# Wave_X_Motor_Drivers.net
KiCad netlist of a schematic drawn in EAGLE
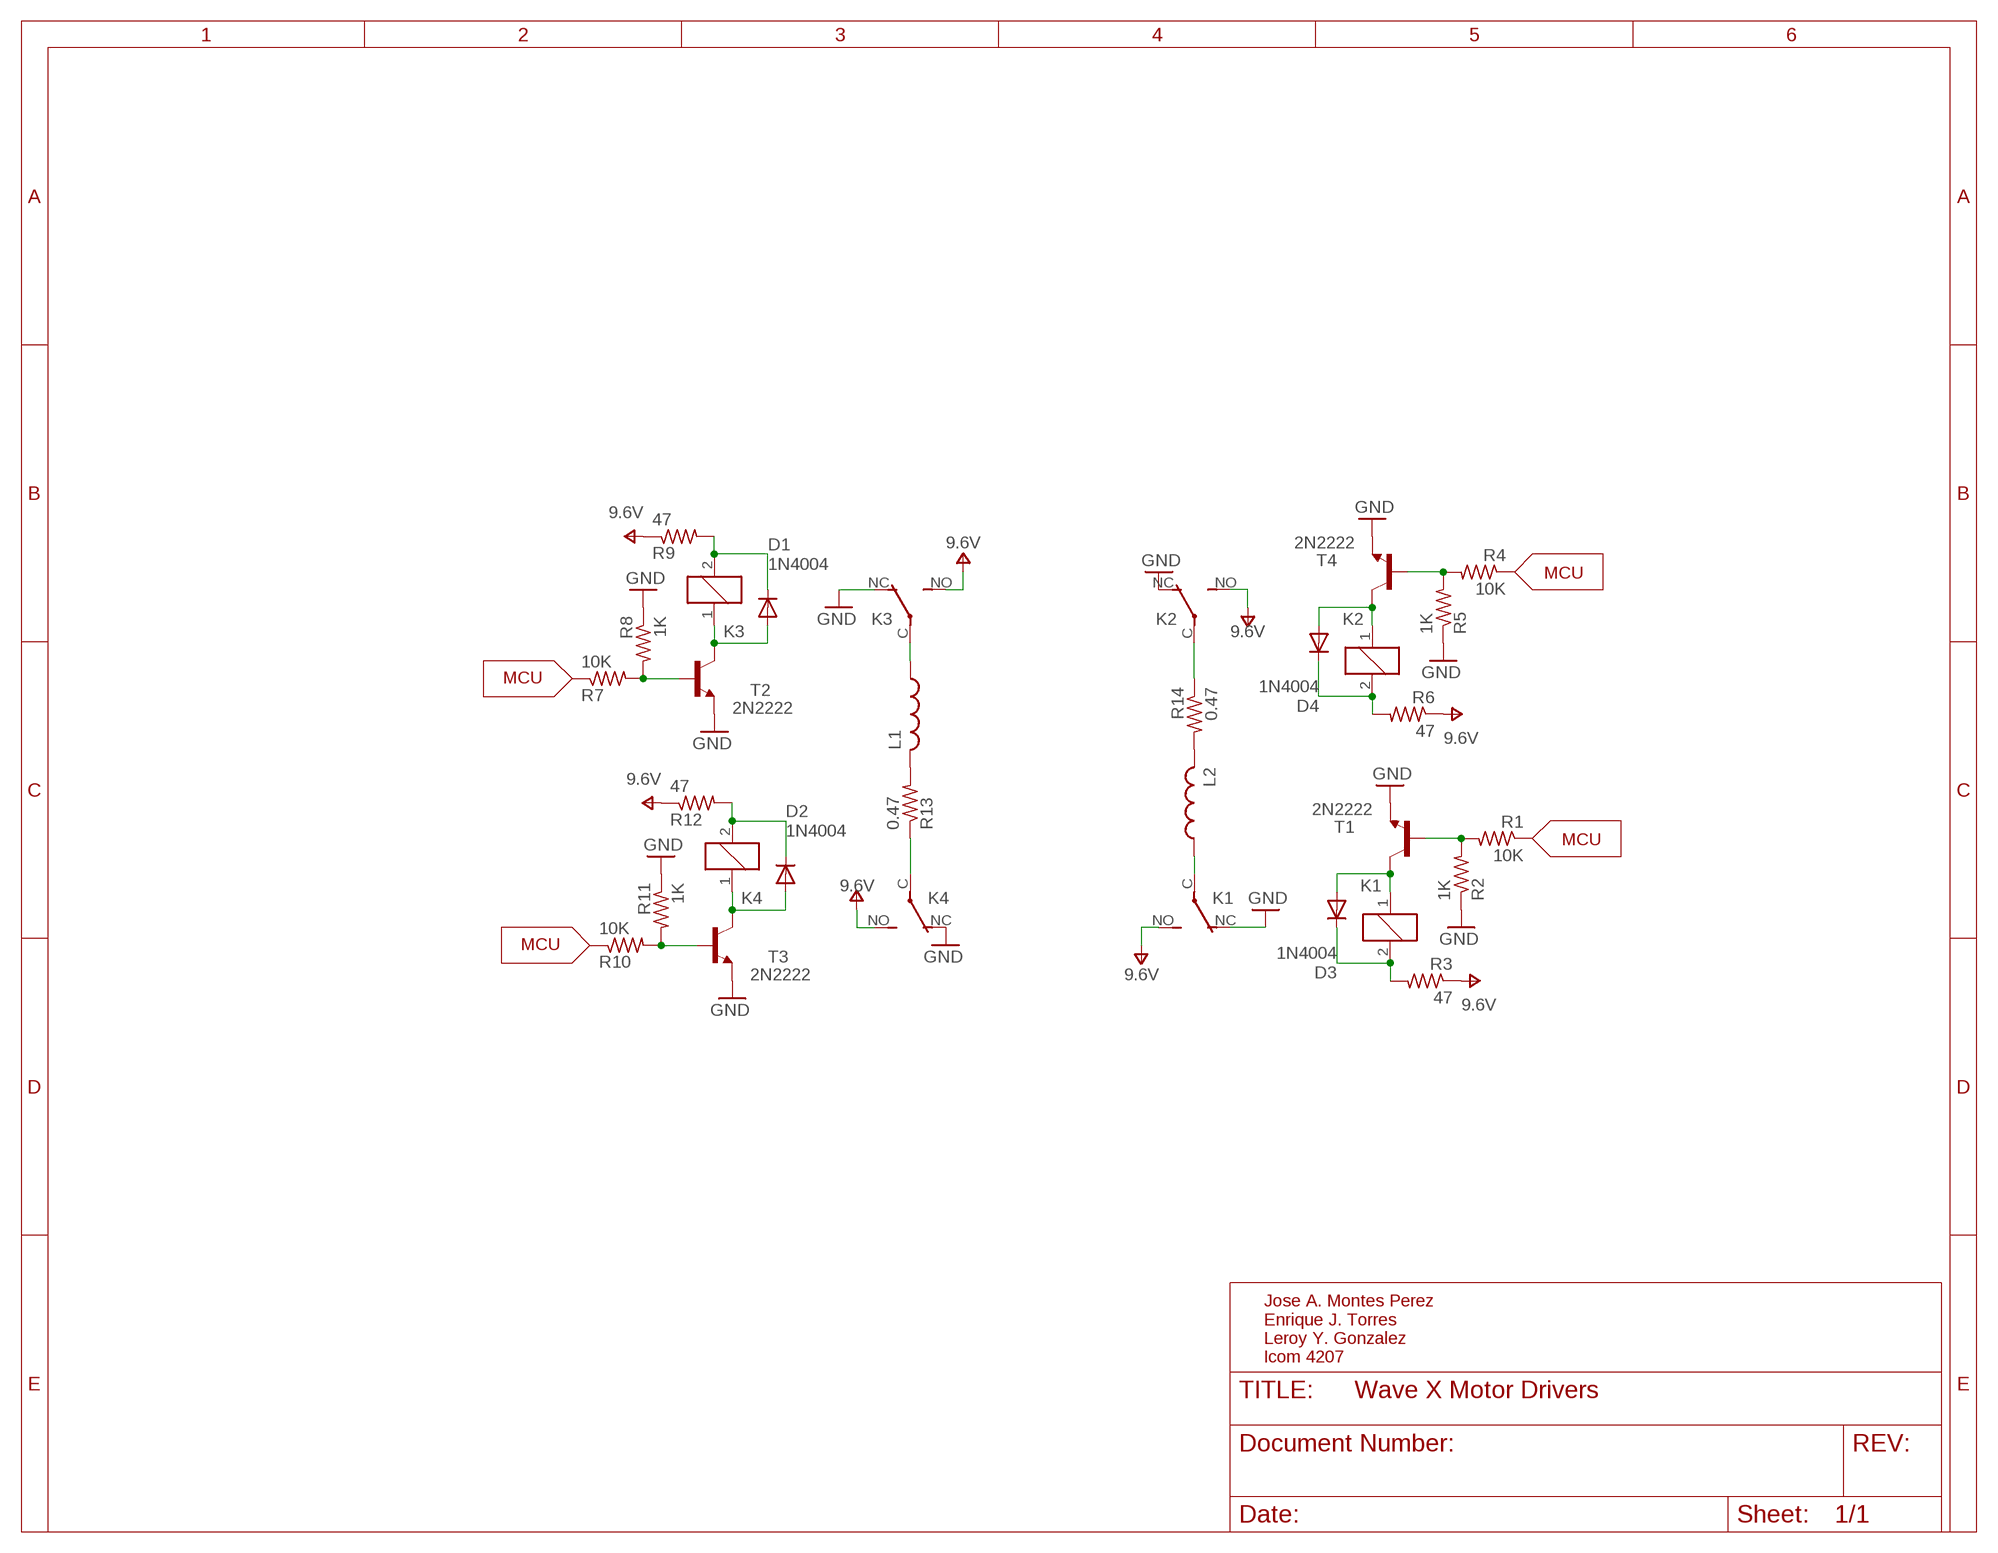
[diagram p0: schematic, sheet 1]

(export (version "E")
  (design (tool "Eeschema 10.0.6"))
  (components
    (comp (ref "D1")
      (value "1N4004")
      (footprint "eagle-import:DO41-10")
      (libsource (lib "eagle-import") (part "1N4004"))
    )
    (comp (ref "D2")
      (value "1N4004")
      (footprint "eagle-import:DO41-10")
      (libsource (lib "eagle-import") (part "1N4004"))
    )
    (comp (ref "D3")
      (value "1N4004")
      (footprint "eagle-import:DO41-10")
      (libsource (lib "eagle-import") (part "1N4004"))
    )
    (comp (ref "D4")
      (value "1N4004")
      (footprint "eagle-import:DO41-10")
      (libsource (lib "eagle-import") (part "1N4004"))
    )
    (comp (ref "K1")
      (value "JJM1-12V")
      (footprint "eagle-import:JJM1C")
      (fields (field (name "MF") "AROMAT/ MATSUSHITA"))
      (libsource (lib "eagle-import") (part "JJM1-12V"))
    )
    (comp (ref "K2")
      (value "JJM1-12V")
      (footprint "eagle-import:JJM1C")
      (fields (field (name "MF") "AROMAT/ MATSUSHITA"))
      (libsource (lib "eagle-import") (part "JJM1-12V"))
    )
    (comp (ref "K3")
      (value "JJM1-12V")
      (footprint "eagle-import:JJM1C")
      (fields (field (name "MF") "AROMAT/ MATSUSHITA"))
      (libsource (lib "eagle-import") (part "JJM1-12V"))
    )
    (comp (ref "K4")
      (value "JJM1-12V")
      (footprint "eagle-import:JJM1C")
      (fields (field (name "MF") "AROMAT/ MATSUSHITA"))
      (libsource (lib "eagle-import") (part "JJM1-12V"))
    )
    (comp (ref "L1")
      (value "L-USL4532P")
      (footprint "eagle-import:L4532P")
      (libsource (lib "eagle-import") (part "L-USL4532P"))
    )
    (comp (ref "L2")
      (value "L-USL4532P")
      (footprint "eagle-import:L4532P")
      (libsource (lib "eagle-import") (part "L-USL4532P"))
    )
    (comp (ref "R1")
      (value "10K")
      (footprint "eagle-import:0207_7")
      (libsource (lib "eagle-import") (part "R-US_0207/7"))
    )
    (comp (ref "R2")
      (value "1K")
      (footprint "eagle-import:0207_7")
      (libsource (lib "eagle-import") (part "R-US_0207/7"))
    )
    (comp (ref "R3")
      (value "47")
      (footprint "eagle-import:0207_7")
      (libsource (lib "eagle-import") (part "R-US_0207/7"))
    )
    (comp (ref "R4")
      (value "10K")
      (footprint "eagle-import:0207_7")
      (libsource (lib "eagle-import") (part "R-US_0207/7"))
    )
    (comp (ref "R5")
      (value "1K")
      (footprint "eagle-import:0207_7")
      (libsource (lib "eagle-import") (part "R-US_0207/7"))
    )
    (comp (ref "R6")
      (value "47")
      (footprint "eagle-import:0207_7")
      (libsource (lib "eagle-import") (part "R-US_0207/7"))
    )
    (comp (ref "R7")
      (value "10K")
      (footprint "eagle-import:0207_7")
      (libsource (lib "eagle-import") (part "R-US_0207/7"))
    )
    (comp (ref "R8")
      (value "1K")
      (footprint "eagle-import:0207_7")
      (libsource (lib "eagle-import") (part "R-US_0207/7"))
    )
    (comp (ref "R9")
      (value "47")
      (footprint "eagle-import:0207_7")
      (libsource (lib "eagle-import") (part "R-US_0207/7"))
    )
    (comp (ref "R10")
      (value "10K")
      (footprint "eagle-import:0207_7")
      (libsource (lib "eagle-import") (part "R-US_0207/7"))
    )
    (comp (ref "R11")
      (value "1K")
      (footprint "eagle-import:0207_7")
      (libsource (lib "eagle-import") (part "R-US_0207/7"))
    )
    (comp (ref "R12")
      (value "47")
      (footprint "eagle-import:0207_7")
      (libsource (lib "eagle-import") (part "R-US_0207/7"))
    )
    (comp (ref "R13")
      (value "0.47")
      (footprint "eagle-import:0207_7")
      (libsource (lib "eagle-import") (part "R-US_0207/7"))
    )
    (comp (ref "R14")
      (value "0.47")
      (footprint "eagle-import:0207_7")
      (libsource (lib "eagle-import") (part "R-US_0207/7"))
    )
    (comp (ref "T1")
      (value "2N2222")
      (footprint "eagle-import:TO18")
      (libsource (lib "eagle-import") (part "2N2222"))
    )
    (comp (ref "T2")
      (value "2N2222")
      (footprint "eagle-import:TO18")
      (libsource (lib "eagle-import") (part "2N2222"))
    )
    (comp (ref "T3")
      (value "2N2222")
      (footprint "eagle-import:TO18")
      (libsource (lib "eagle-import") (part "2N2222"))
    )
    (comp (ref "T4")
      (value "2N2222")
      (footprint "eagle-import:TO18")
      (libsource (lib "eagle-import") (part "2N2222"))
    )
  )
  (nets
    (net (code "1") (name "9.6V") (class "Default")
      (node (ref "K1") (pin "NO") (pinfunction "S_NO") (pintype "passive"))
      (node (ref "K2") (pin "NO") (pinfunction "S_NO") (pintype "passive"))
      (node (ref "K3") (pin "NO") (pinfunction "S_NO") (pintype "passive"))
      (node (ref "K4") (pin "NO") (pinfunction "S_NO") (pintype "passive"))
      (node (ref "R12") (pin "1") (pinfunction "1_1") (pintype "passive"))
      (node (ref "R3") (pin "1") (pinfunction "1_1") (pintype "passive"))
      (node (ref "R6") (pin "1") (pinfunction "1_1") (pintype "passive"))
      (node (ref "R9") (pin "1") (pinfunction "1_1") (pintype "passive"))
    )
    (net (code "2") (name "GND") (class "Default")
      (node (ref "K1") (pin "NC") (pinfunction "O_NC") (pintype "passive"))
      (node (ref "K2") (pin "NC") (pinfunction "O_NC") (pintype "passive"))
      (node (ref "K3") (pin "NC") (pinfunction "O_NC") (pintype "passive"))
      (node (ref "K4") (pin "NC") (pinfunction "O_NC") (pintype "passive"))
      (node (ref "R11") (pin "1") (pinfunction "1_1") (pintype "passive"))
      (node (ref "R2") (pin "1") (pinfunction "1_1") (pintype "passive"))
      (node (ref "R5") (pin "1") (pinfunction "1_1") (pintype "passive"))
      (node (ref "R8") (pin "1") (pinfunction "1_1") (pintype "passive"))
      (node (ref "T1") (pin "1") (pinfunction "E_1") (pintype "passive"))
      (node (ref "T2") (pin "1") (pinfunction "E_1") (pintype "passive"))
      (node (ref "T3") (pin "1") (pinfunction "E_1") (pintype "passive"))
      (node (ref "T4") (pin "1") (pinfunction "E_1") (pintype "passive"))
    )
    (net (code "3") (name "Net-(D1-PadC)") (class "Default")
      (node (ref "D1") (pin "C") (pinfunction "C_C") (pintype "passive"))
      (node (ref "K3") (pin "2") (pinfunction "2_2") (pintype "passive"))
      (node (ref "R9") (pin "2") (pinfunction "2_2") (pintype "passive"))
    )
    (net (code "4") (name "Net-(D2-PadC)") (class "Default")
      (node (ref "D2") (pin "C") (pinfunction "C_C") (pintype "passive"))
      (node (ref "K4") (pin "2") (pinfunction "2_2") (pintype "passive"))
      (node (ref "R12") (pin "2") (pinfunction "2_2") (pintype "passive"))
    )
    (net (code "5") (name "Net-(D3-PadC)") (class "Default")
      (node (ref "D3") (pin "C") (pinfunction "C_C") (pintype "passive"))
      (node (ref "K1") (pin "2") (pinfunction "2_2") (pintype "passive"))
      (node (ref "R3") (pin "2") (pinfunction "2_2") (pintype "passive"))
    )
    (net (code "6") (name "Net-(D4-PadC)") (class "Default")
      (node (ref "D4") (pin "C") (pinfunction "C_C") (pintype "passive"))
      (node (ref "K2") (pin "2") (pinfunction "2_2") (pintype "passive"))
      (node (ref "R6") (pin "2") (pinfunction "2_2") (pintype "passive"))
    )
    (net (code "7") (name "Net-(K1B-P)") (class "Default")
      (node (ref "K1") (pin "C") (pinfunction "P_C") (pintype "passive"))
      (node (ref "L2") (pin "1") (pinfunction "1_1") (pintype "passive"))
    )
    (net (code "8") (name "Net-(K2B-P)") (class "Default")
      (node (ref "K2") (pin "C") (pinfunction "P_C") (pintype "passive"))
      (node (ref "R14") (pin "1") (pinfunction "1_1") (pintype "passive"))
    )
    (net (code "9") (name "Net-(K3B-P)") (class "Default")
      (node (ref "K3") (pin "C") (pinfunction "P_C") (pintype "passive"))
      (node (ref "L1") (pin "1") (pinfunction "1_1") (pintype "passive"))
    )
    (net (code "10") (name "Net-(K4B-P)") (class "Default")
      (node (ref "K4") (pin "C") (pinfunction "P_C") (pintype "passive"))
      (node (ref "R13") (pin "1") (pinfunction "1_1") (pintype "passive"))
    )
    (net (code "11") (name "Net-(L1-Pad2)") (class "Default")
      (node (ref "L1") (pin "2") (pinfunction "2_2") (pintype "passive"))
      (node (ref "R13") (pin "2") (pinfunction "2_2") (pintype "passive"))
    )
    (net (code "12") (name "Net-(L2-Pad2)") (class "Default")
      (node (ref "L2") (pin "2") (pinfunction "2_2") (pintype "passive"))
      (node (ref "R14") (pin "2") (pinfunction "2_2") (pintype "passive"))
    )
    (net (code "13") (name "Net-(T1-B)") (class "Default")
      (node (ref "R1") (pin "2") (pinfunction "2_2") (pintype "passive"))
      (node (ref "R2") (pin "2") (pinfunction "2_2") (pintype "passive"))
      (node (ref "T1") (pin "2") (pinfunction "B_2") (pintype "passive"))
    )
    (net (code "14") (name "Net-(T1-C)") (class "Default")
      (node (ref "D3") (pin "A") (pinfunction "A_A") (pintype "passive"))
      (node (ref "K1") (pin "1") (pinfunction "1_1") (pintype "passive"))
      (node (ref "T1") (pin "3") (pinfunction "C_3") (pintype "passive"))
    )
    (net (code "15") (name "Net-(T2-B)") (class "Default")
      (node (ref "R7") (pin "2") (pinfunction "2_2") (pintype "passive"))
      (node (ref "R8") (pin "2") (pinfunction "2_2") (pintype "passive"))
      (node (ref "T2") (pin "2") (pinfunction "B_2") (pintype "passive"))
    )
    (net (code "16") (name "Net-(T2-C)") (class "Default")
      (node (ref "D1") (pin "A") (pinfunction "A_A") (pintype "passive"))
      (node (ref "K3") (pin "1") (pinfunction "1_1") (pintype "passive"))
      (node (ref "T2") (pin "3") (pinfunction "C_3") (pintype "passive"))
    )
    (net (code "17") (name "Net-(T3-B)") (class "Default")
      (node (ref "R10") (pin "2") (pinfunction "2_2") (pintype "passive"))
      (node (ref "R11") (pin "2") (pinfunction "2_2") (pintype "passive"))
      (node (ref "T3") (pin "2") (pinfunction "B_2") (pintype "passive"))
    )
    (net (code "18") (name "Net-(T3-C)") (class "Default")
      (node (ref "D2") (pin "A") (pinfunction "A_A") (pintype "passive"))
      (node (ref "K4") (pin "1") (pinfunction "1_1") (pintype "passive"))
      (node (ref "T3") (pin "3") (pinfunction "C_3") (pintype "passive"))
    )
    (net (code "19") (name "Net-(T4-B)") (class "Default")
      (node (ref "R4") (pin "2") (pinfunction "2_2") (pintype "passive"))
      (node (ref "R5") (pin "2") (pinfunction "2_2") (pintype "passive"))
      (node (ref "T4") (pin "2") (pinfunction "B_2") (pintype "passive"))
    )
    (net (code "20") (name "Net-(T4-C)") (class "Default")
      (node (ref "D4") (pin "A") (pinfunction "A_A") (pintype "passive"))
      (node (ref "K2") (pin "1") (pinfunction "1_1") (pintype "passive"))
      (node (ref "T4") (pin "3") (pinfunction "C_3") (pintype "passive"))
    )
    (net (code "21") (name "unconnected-(R1-Pad1)") (class "Default")
      (node (ref "R1") (pin "1") (pinfunction "1_1") (pintype "passive"))
    )
    (net (code "22") (name "unconnected-(R4-Pad1)") (class "Default")
      (node (ref "R4") (pin "1") (pinfunction "1_1") (pintype "passive"))
    )
    (net (code "23") (name "unconnected-(R7-Pad1)") (class "Default")
      (node (ref "R7") (pin "1") (pinfunction "1_1") (pintype "passive"))
    )
    (net (code "24") (name "unconnected-(R10-Pad1)") (class "Default")
      (node (ref "R10") (pin "1") (pinfunction "1_1") (pintype "passive"))
    )
  )
)
